# Modulo_Micro_Starter.net
KiCad netlist of a schematic drawn in Altium Designer
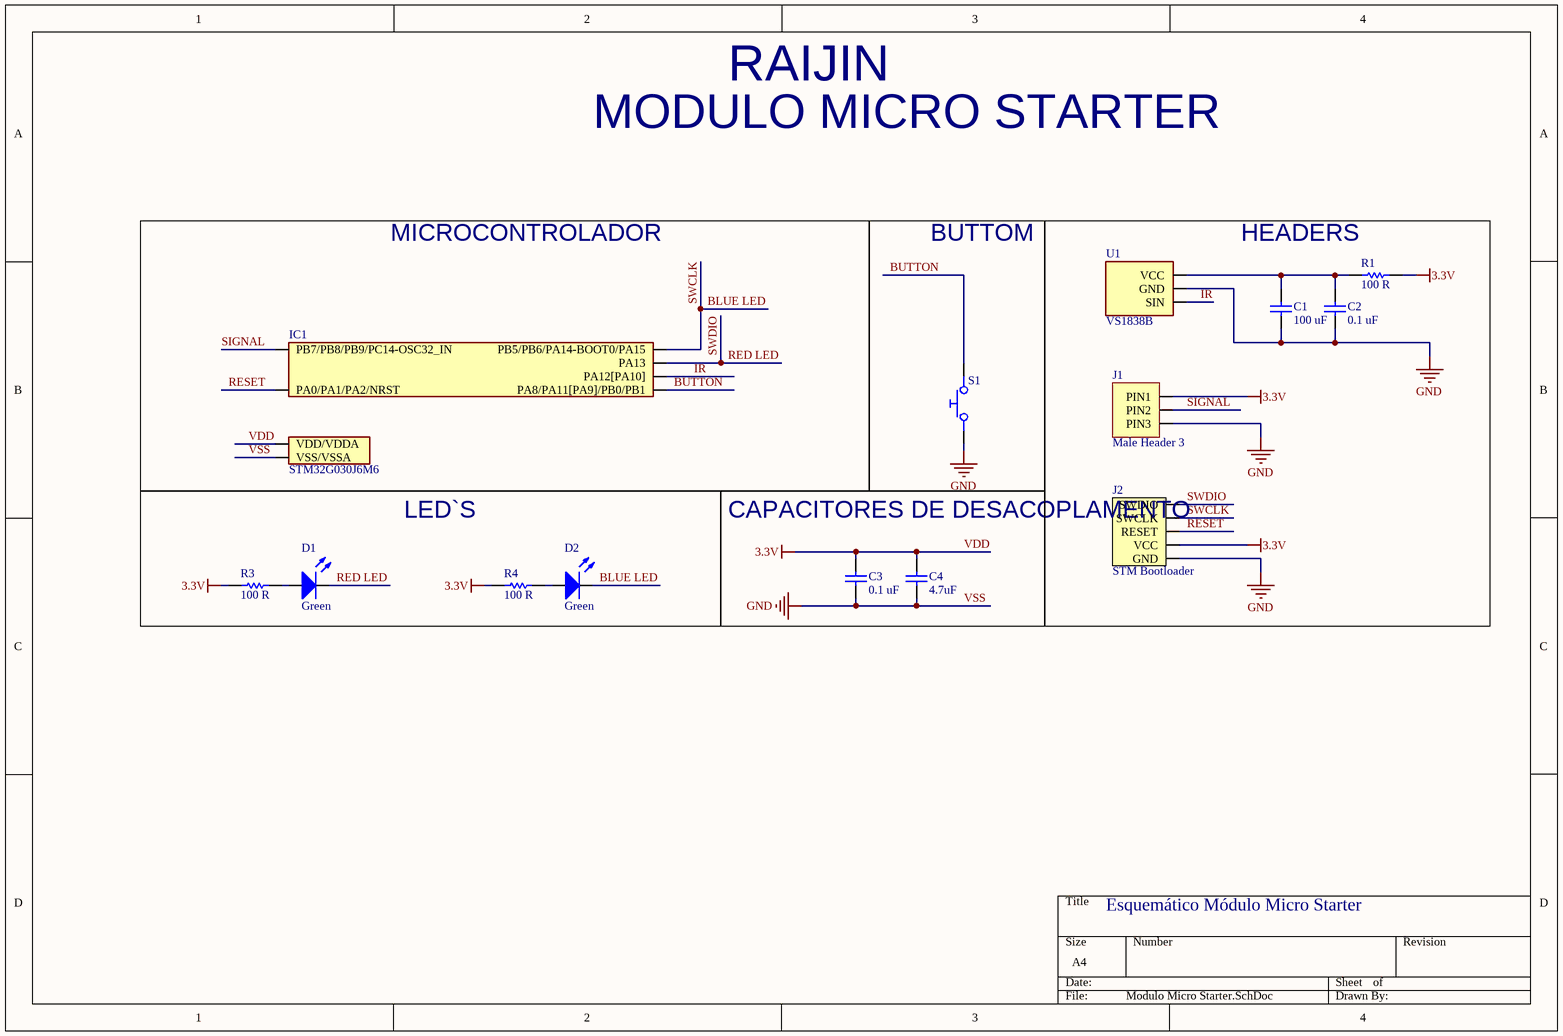
[diagram p0: Modulo Micro Starter.SchDoc]

(export (version "E")
  (design (tool "Eeschema 10.0.6"))
  (components
    (comp (ref "C1")
      (value "100 uF")
      (footprint "C0805")
      (description "CAP CER 100UF 6.3V X5R 0805")
      (fields
        (field (name "MANUFACTURER") "TAIYO YUDEN")
        (field (name "PART NUMBER") "JMK212BBJ107MGTE")
        (field (name "LIBRARY CONTROL - PERSON THAT CHECKED FOOTPRINT") "Nikaum")
        (field (name "LIBRARY CONTROL - PERSON THAT CHECKED SCHEMATIC") "Nikaum")
        (field (name "LIBRARY CONTROL - PERSON THAT DID THE LAST UPDATE FOOTPRINT") "Nikaum")
        (field (name "LIBRARY CONTROL - PERSON THAT DID THE LAST UPDATE SCHEMATIC") "Nikaum")
      )
      (libsource (lib "Uai!Tecas") (part "JMK212BBJ107MG-TE"))
    )
    (comp (ref "C2")
      (value "0.1 uF")
      (footprint "C0603")
      (description "CAP CER 0.1uF 25V X7R 0603")
      (fields
        (field (name "MANUFACTURER") "Murata Electronics")
        (field (name "PART NUMBER") "GRM188R71E104KA01D")
        (field (name "LIBRARY CONTROL - PERSON THAT CHECKED FOOTPRINT") "Nikaum")
        (field (name "LIBRARY CONTROL - PERSON THAT CHECKED SCHEMATIC") "Nikaum")
        (field (name "LIBRARY CONTROL - PERSON THAT DID THE LAST UPDATE FOOTPRINT") "Raquel")
        (field (name "LIBRARY CONTROL - PERSON THAT DID THE LAST UPDATE SCHEMATIC") "Nikaum")
      )
      (libsource (lib "Uai!Tecas") (part "GRM188R71E104KA01D"))
    )
    (comp (ref "C3")
      (value "0.1 uF")
      (footprint "C0603")
      (description "CAP CER 0.1uF 25V X7R 0603")
      (fields
        (field (name "MANUFACTURER") "Murata Electronics")
        (field (name "PART NUMBER") "GRM188R71E104KA01D")
        (field (name "LIBRARY CONTROL - PERSON THAT CHECKED FOOTPRINT") "Nikaum")
        (field (name "LIBRARY CONTROL - PERSON THAT CHECKED SCHEMATIC") "Nikaum")
        (field (name "LIBRARY CONTROL - PERSON THAT DID THE LAST UPDATE FOOTPRINT") "Raquel")
        (field (name "LIBRARY CONTROL - PERSON THAT DID THE LAST UPDATE SCHEMATIC") "Nikaum")
      )
      (libsource (lib "Uai!Tecas") (part "GRM188R71E104KA01D"))
    )
    (comp (ref "C4")
      (value "4.7uF")
      (footprint "C0603")
      (description "CAP CER 4.7uF 25V X5R 0603")
      (fields
        (field (name "MANUFACTURER") "Yageo")
        (field (name "PART NUMBER") "CC0603KRX5R8BB475")
        (field (name "LIBRARY CONTROL - PERSON THAT CHECKED FOOTPRINT") "Nikaum")
        (field (name "LIBRARY CONTROL - PERSON THAT CHECKED SCHEMATIC") "Nikaum")
        (field (name "LIBRARY CONTROL - PERSON THAT DID THE LAST UPDATE FOOTPRINT") "Nikaum")
        (field (name "LIBRARY CONTROL - PERSON THAT DID THE LAST UPDATE SCHEMATIC") "Nikaum")
      )
      (libsource (lib "Uai!Tecas") (part "CC0603KRX5R8BB475"))
    )
    (comp (ref "D1")
      (value "Green")
      (footprint "LED_0603")
      (description "LED 0.072W GREEN 40MCD 0603")
      (fields
        (field (name "MANUFACTURER") "Wurth Elektronik")
        (field (name "MANUFACTURER PART NUMBER") "150060VS75000")
        (field (name "LIBRARY CONTROL - PERSON THAT CHECKED FOOTPRINT") "Nícolas")
        (field (name "LIBRARY CONTROL - PERSON THAT CHECKED SCHEMATIC") "Nícolas")
        (field (name "LIBRARY CONTROL - PERSON THAT DID THE LAST UPDATE FOOTPRINT") "Marcos")
        (field (name "LIBRARY CONTROL - PERSON THAT DID THE LAST UPDATE SCHEMATIC") "Marcos")
      )
      (libsource (lib "Uai!Tecas") (part "150060VS75000"))
    )
    (comp (ref "D2")
      (value "Green")
      (footprint "LED_0603")
      (description "LED 0.072W GREEN 40MCD 0603")
      (fields
        (field (name "MANUFACTURER") "Wurth Elektronik")
        (field (name "MANUFACTURER PART NUMBER") "150060VS75000")
        (field (name "LIBRARY CONTROL - PERSON THAT CHECKED FOOTPRINT") "Nícolas")
        (field (name "LIBRARY CONTROL - PERSON THAT CHECKED SCHEMATIC") "Nícolas")
        (field (name "LIBRARY CONTROL - PERSON THAT DID THE LAST UPDATE FOOTPRINT") "Marcos")
        (field (name "LIBRARY CONTROL - PERSON THAT DID THE LAST UPDATE SCHEMATIC") "Marcos")
      )
      (libsource (lib "Uai!Tecas") (part "150060VS75000"))
    )
    (comp (ref "IC1")
      (value "STM32G030J6M6")
      (footprint "SO8N")
      (description "IC MCU 32-BIT 8kB FLASH ARM Cortex M0+ 64MHZ  SO8N")
      (fields
        (field (name "MANUFACTURER") "STM")
        (field (name "LIBRARY CONTROL - PERSON THAT DID THE LAST UPDATE FOOTPRINT") "Marcos")
        (field (name "LIBRARY CONTROL - PERSON THAT DID THE LAST UPDATE SCHEMATIC") "Marcos")
      )
      (libsource (lib "Microcontrolador") (part "STM32G030J6M6"))
    )
    (comp (ref "J1")
      (value "Male Header 3")
      (footprint "MALE HEADER 3")
      (fields
        (field (name "LIBRARY CONTROL - PERSON THAT DID THE LAST UPDATE SCHEMATIC") "Guilherme")
        (field (name "LIBRARY CONTROL - PERSONT THAT DID THE LAST UPDATE FOOTPRINT") "Guilherme")
      )
      (libsource (lib "Header") (part "Male Header 3"))
    )
    (comp (ref "J2")
      (value "STM Bootloader")
      (footprint "STM BOOTLOADER")
      (description "BARRAMENTO DE GRAVAÇÃO")
      (libsource (lib "Uai!Tecas") (part "Barramento de Gravação STM"))
    )
    (comp (ref "R1")
      (value "100 R")
      (footprint "RESISTOR_0603")
      (description "RES SMD 100 OHM 1% 1/10W 0603")
      (fields
        (field (name "MANUFACTURER") "Yageo")
        (field (name "PART NUMBER") "RC0603FR-10100RL")
        (field (name "LIBRARY CONTROL - PERSON THAT CHECKED FOOTPRINT") "Nikaum")
        (field (name "LIBRARY CONTROL - PERSON THAT CHECKED SCHEMATIC") "Nikaum")
        (field (name "LIBRARY CONTROL - PERSON THAT DID THE LAST UPDATE FOOTPRINT") "Nicolas")
        (field (name "LIBRARY CONTROL - PERSON THAT DID THE LAST UPDATE SCHEMATIC") "Nikaum")
      )
      (libsource (lib "Uai!Tecas") (part "RC0603FR-10100RL"))
    )
    (comp (ref "R3")
      (value "100 R")
      (footprint "RESISTOR_0603")
      (description "RES SMD 100 OHM 1% 1/10W 0603")
      (fields
        (field (name "MANUFACTURER") "Yageo")
        (field (name "PART NUMBER") "RC0603FR-10100RL")
        (field (name "LIBRARY CONTROL - PERSON THAT CHECKED FOOTPRINT") "Nikaum")
        (field (name "LIBRARY CONTROL - PERSON THAT CHECKED SCHEMATIC") "Nikaum")
        (field (name "LIBRARY CONTROL - PERSON THAT DID THE LAST UPDATE FOOTPRINT") "Nicolas")
        (field (name "LIBRARY CONTROL - PERSON THAT DID THE LAST UPDATE SCHEMATIC") "Nikaum")
      )
      (libsource (lib "Uai!Tecas") (part "RC0603FR-10100RL"))
    )
    (comp (ref "R4")
      (value "100 R")
      (footprint "RESISTOR_0603")
      (description "RES SMD 100 OHM 1% 1/10W 0603")
      (fields
        (field (name "MANUFACTURER") "Yageo")
        (field (name "PART NUMBER") "RC0603FR-10100RL")
        (field (name "LIBRARY CONTROL - PERSON THAT CHECKED FOOTPRINT") "Nikaum")
        (field (name "LIBRARY CONTROL - PERSON THAT CHECKED SCHEMATIC") "Nikaum")
        (field (name "LIBRARY CONTROL - PERSON THAT DID THE LAST UPDATE FOOTPRINT") "Nicolas")
        (field (name "LIBRARY CONTROL - PERSON THAT DID THE LAST UPDATE SCHEMATIC") "Nikaum")
      )
      (libsource (lib "Uai!Tecas") (part "RC0603FR-10100RL"))
    )
    (comp (ref "S1")
      (value "PTS540JK035SMTRLFS")
      (footprint "PUSH_BUTTON")
      (description "TACTILE SWITCH SPST 0.05A 12VDC SMD")
      (fields
        (field (name "MANUFACTURER") "C&K Switches")
        (field (name "LIBRARY CONTROL - PERSON THAT CHECKED SCHEMATIC") "Nícolas")
        (field (name "LIBRARY CONTROL - PERSON THAT CHECKED FOOTPRINT") "Nícolas")
        (field (name "LIBRARY CONTROL - PERSON THAT DID THE LAST UPDATE SCHEMATIC") "Nícolas")
      )
      (libsource (lib "Uai!Tecas") (part "Push Button"))
    )
    (comp (ref "U1")
      (value "VS1838B")
      (footprint "FEMALE HEADER 3")
      (description "INFRARED RECEIVER MODULE")
      (fields
        (field (name "LIBRARY CONTROL - PERSON THAT DID THE LAST UPDATE IN FOOTPRINT") "Marcos")
        (field (name "LIBRARY CONTROL - PERSON THAT DID THE LAST UPDATE IN SCHEMATIC") "Marcos")
      )
      (libsource (lib "Uai!Tecas") (part "VS1838B"))
    )
  )
  (nets
    (net (code "1") (name "/BLUE LED") (class "Default")
      (node (ref "D2") (pin "C") (pinfunction "C_C") (pintype "passive"))
      (node (ref "IC1") (pin "8") (pinfunction "PB5/PB6/PA14-BOOT0/PA15_8") (pintype "passive"))
      (node (ref "J2") (pin "CLK") (pinfunction "SWCLK_CLK") (pintype "passive"))
    )
    (net (code "2") (name "/BUTTON") (class "Default")
      (node (ref "IC1") (pin "5") (pinfunction "PA8/PA11[PA9]/PB0/PB1_5") (pintype "passive"))
      (node (ref "S1") (pin "2") (pinfunction "2_2") (pintype "passive"))
    )
    (net (code "3") (name "/IR") (class "Default")
      (node (ref "IC1") (pin "6") (pinfunction "PA12[PA10]_6") (pintype "passive"))
      (node (ref "U1") (pin "PIN3") (pinfunction "SIN_PIN3") (pintype "passive"))
    )
    (net (code "4") (name "/RED LED") (class "Default")
      (node (ref "D1") (pin "C") (pinfunction "C_C") (pintype "passive"))
      (node (ref "IC1") (pin "7") (pinfunction "PA13_7") (pintype "passive"))
      (node (ref "J2") (pin "DIO") (pinfunction "SWDIO_DIO") (pintype "passive"))
    )
    (net (code "5") (name "/RESET") (class "Default")
      (node (ref "IC1") (pin "4") (pinfunction "PA0/PA1/PA2/NRST_4") (pintype "passive"))
      (node (ref "J2") (pin "RESET") (pinfunction "RESET_RESET") (pintype "passive"))
    )
    (net (code "6") (name "/SIGNAL") (class "Default")
      (node (ref "IC1") (pin "1") (pinfunction "PB7/PB8/PB9/PC14-OSC32_IN_1") (pintype "passive"))
      (node (ref "J1") (pin "PIN2") (pinfunction "PIN2_PIN2") (pintype "passive"))
    )
    (net (code "7") (name "3.3V") (class "Default")
      (node (ref "C3") (pin "2") (pinfunction "2_2") (pintype "passive"))
      (node (ref "C4") (pin "2") (pinfunction "2_2") (pintype "passive"))
      (node (ref "IC1") (pin "2") (pinfunction "VDD/VDDA_2") (pintype "passive"))
      (node (ref "J1") (pin "PIN1") (pinfunction "PIN1_PIN1") (pintype "passive"))
      (node (ref "J2") (pin "VCC") (pinfunction "VCC_VCC") (pintype "passive"))
      (node (ref "R1") (pin "2") (pinfunction "2_2") (pintype "passive"))
      (node (ref "R3") (pin "1") (pinfunction "1_1") (pintype "passive"))
      (node (ref "R4") (pin "1") (pinfunction "1_1") (pintype "passive"))
    )
    (net (code "8") (name "GND") (class "Default")
      (node (ref "C1") (pin "1") (pinfunction "1_1") (pintype "passive"))
      (node (ref "C2") (pin "1") (pinfunction "1_1") (pintype "passive"))
      (node (ref "C3") (pin "1") (pinfunction "1_1") (pintype "passive"))
      (node (ref "C4") (pin "1") (pinfunction "1_1") (pintype "passive"))
      (node (ref "IC1") (pin "3") (pinfunction "VSS/VSSA_3") (pintype "passive"))
      (node (ref "J1") (pin "PIN3") (pinfunction "PIN3_PIN3") (pintype "passive"))
      (node (ref "J2") (pin "GND") (pinfunction "GND_GND") (pintype "passive"))
      (node (ref "S1") (pin "1") (pinfunction "1_1") (pintype "passive"))
      (node (ref "U1") (pin "PIN2") (pinfunction "GND_PIN2") (pintype "passive"))
    )
    (net (code "9") (name "Net-(D1-PadA)") (class "Default")
      (node (ref "D1") (pin "A") (pinfunction "A_A") (pintype "passive"))
      (node (ref "R3") (pin "2") (pinfunction "2_2") (pintype "passive"))
    )
    (net (code "10") (name "Net-(D2-PadA)") (class "Default")
      (node (ref "D2") (pin "A") (pinfunction "A_A") (pintype "passive"))
      (node (ref "R4") (pin "2") (pinfunction "2_2") (pintype "passive"))
    )
    (net (code "11") (name "Net-(U1-VCC)") (class "Default")
      (node (ref "C1") (pin "2") (pinfunction "2_2") (pintype "passive"))
      (node (ref "C2") (pin "2") (pinfunction "2_2") (pintype "passive"))
      (node (ref "R1") (pin "1") (pinfunction "1_1") (pintype "passive"))
      (node (ref "U1") (pin "PIN1") (pinfunction "VCC_PIN1") (pintype "passive"))
    )
  )
)
